# SCH_USB-Hub-with-audio-card_2025-04-20.net
KiCad netlist of a schematic drawn in EasyEDA
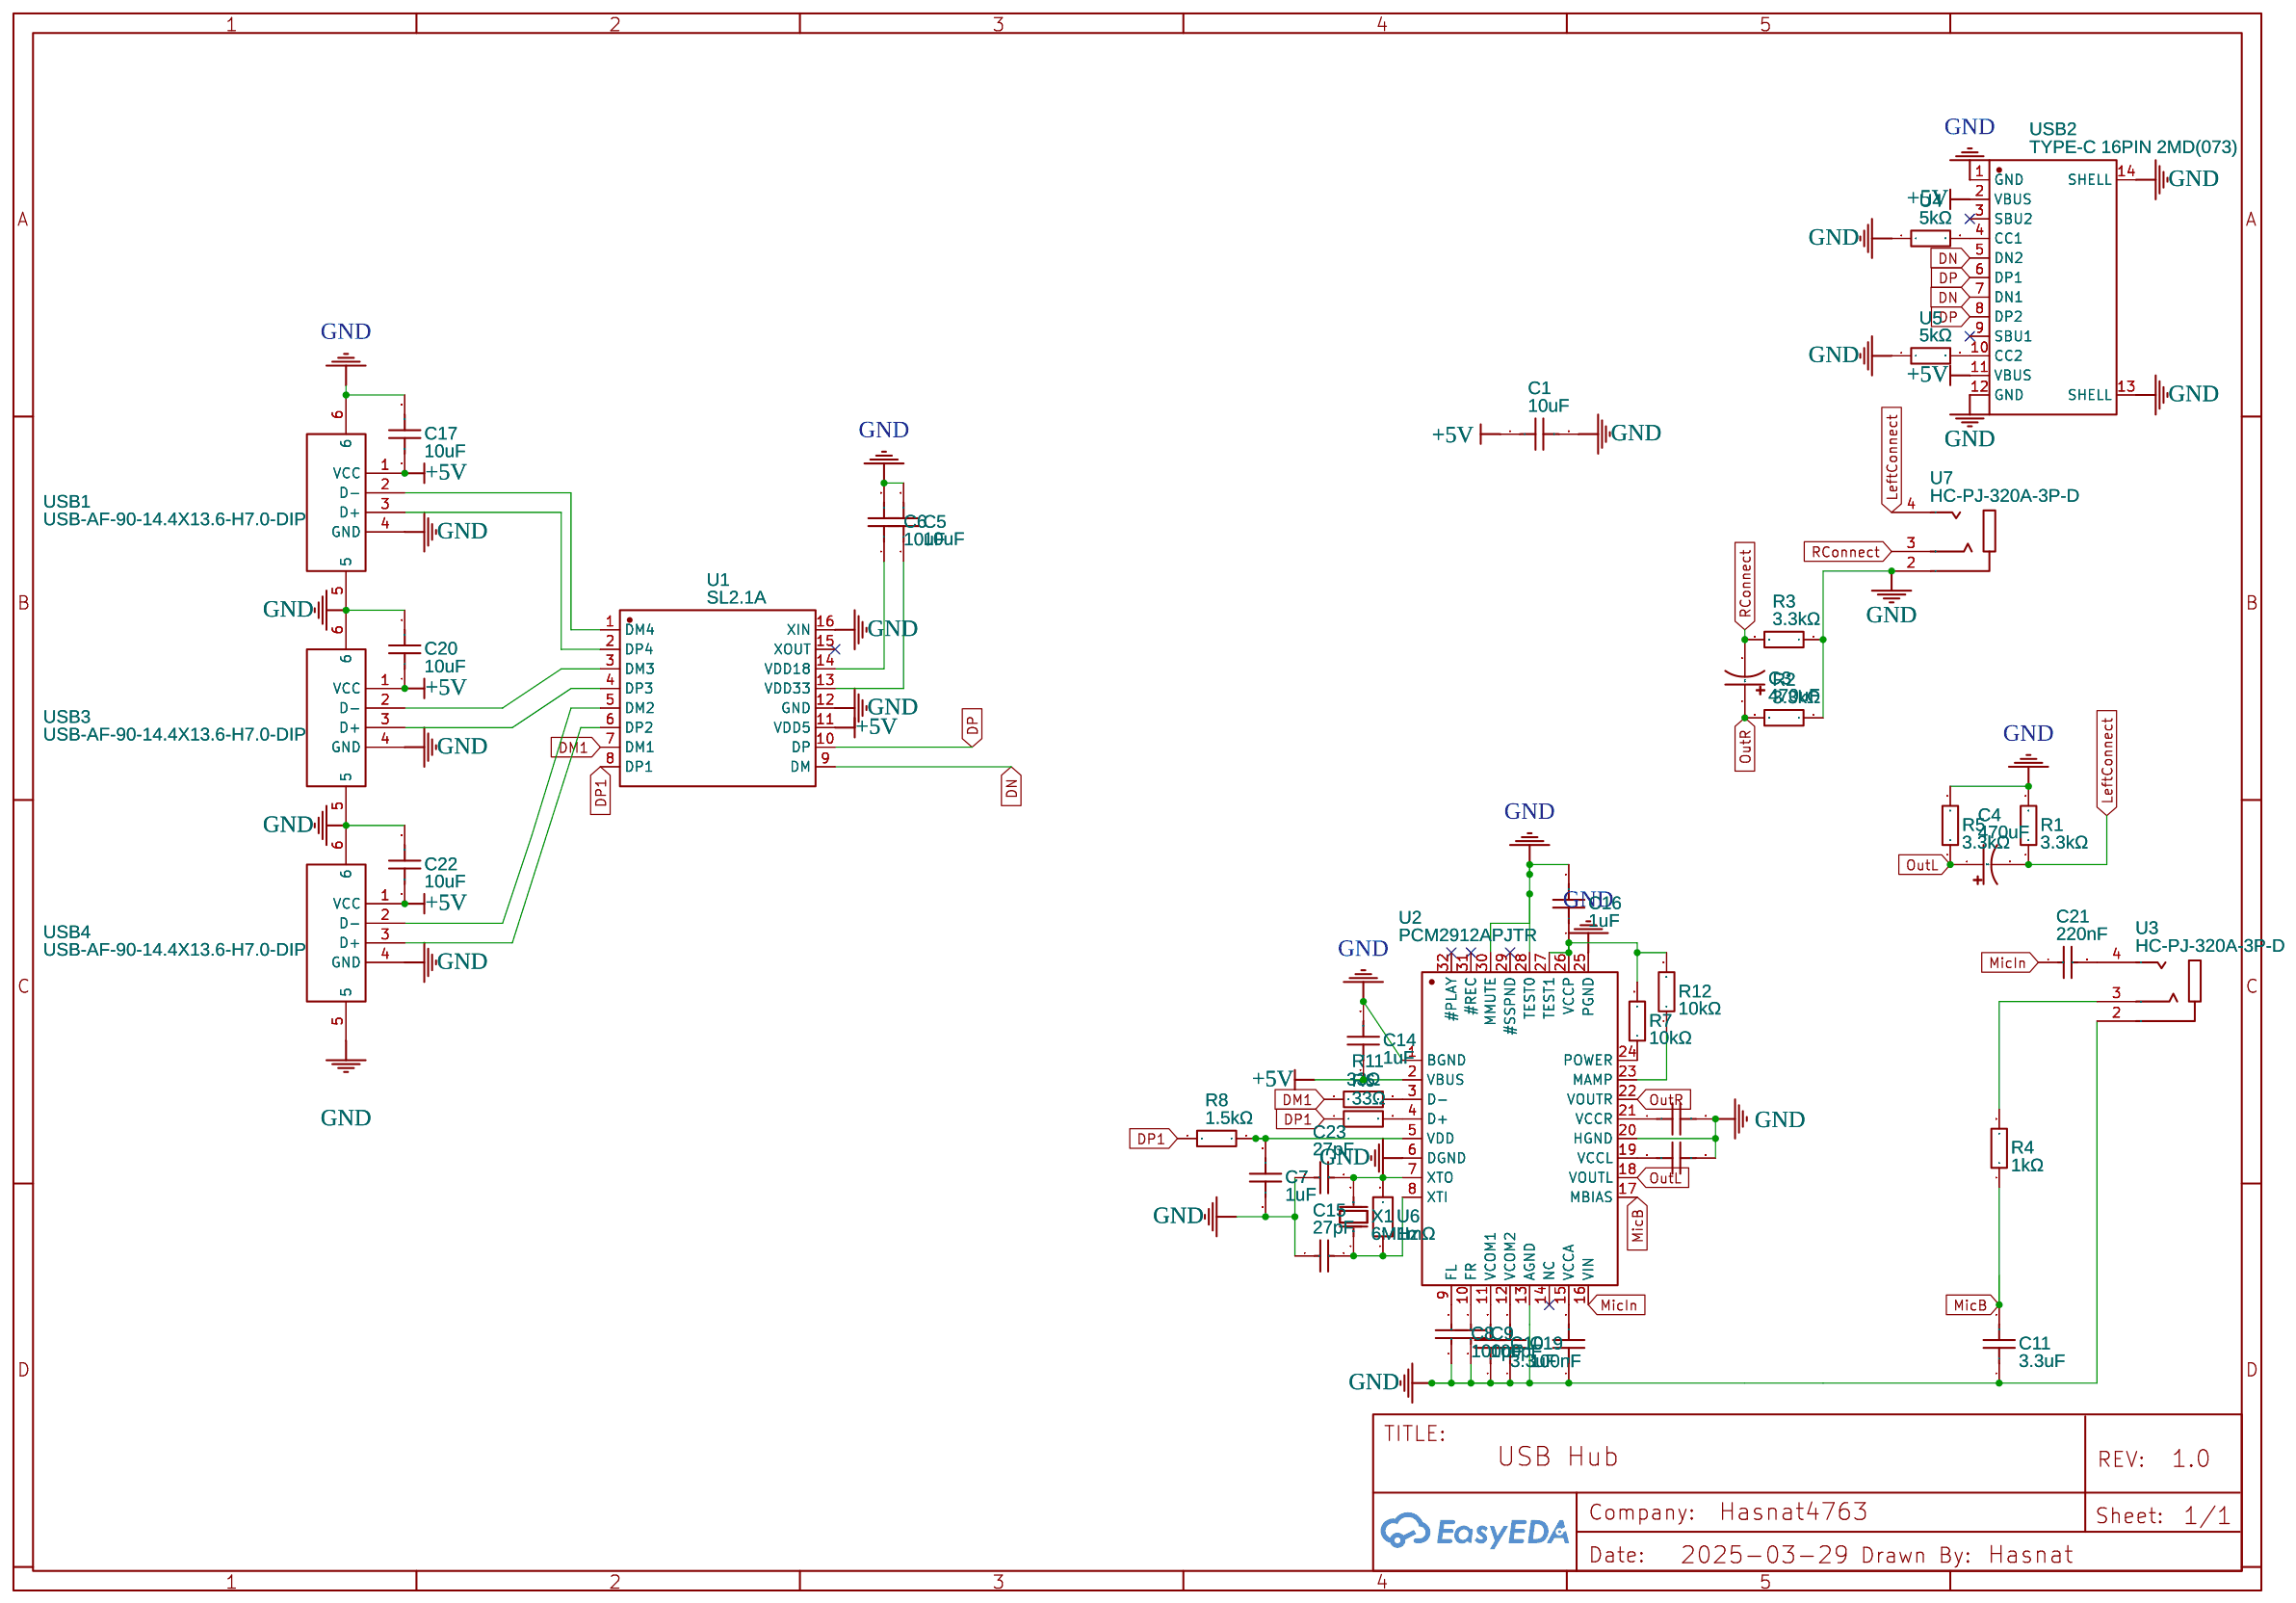
[diagram p0: schematic sheet]

(export (version "E")
  (design (tool "Eeschema 10.0.6"))
  (components
    (comp (ref "C1")
      (value "10uF")
      (fields
        (field (name "Manufacturer Part") "CL10A106KP8NNNC")
        (field (name "Manufacturer") "SAMSUNG(三星)")
      )
      (libsource (lib "") (part "CL10A106KP8NNNC"))
    )
    (comp (ref "C2")
      (value "1uF")
      (fields
        (field (name "Manufacturer Part") "CL31B105KBHNNNE")
        (field (name "Manufacturer") "SAMSUNG(三星)")
      )
      (libsource (lib "") (part "CL31B105KBHNNNE_1"))
    )
    (comp (ref "C3")
      (value "470uF")
      (fields (field (name "Manufacturer Part") "UKW1C471MPD") (field (name "Manufacturer") "Nichicon(尼吉康)"))
      (libsource (lib "") (part "UKW1C471MPD"))
    )
    (comp (ref "C4")
      (value "470uF")
      (fields (field (name "Manufacturer Part") "UKW1C471MPD") (field (name "Manufacturer") "Nichicon(尼吉康)"))
      (libsource (lib "") (part "UKW1C471MPD_1"))
    )
    (comp (ref "C5")
      (value "10uF")
      (fields
        (field (name "Manufacturer Part") "CL10A106KP8NNNC")
        (field (name "Manufacturer") "SAMSUNG(三星)")
      )
      (libsource (lib "") (part "CL10A106KP8NNNC_1"))
    )
    (comp (ref "C6")
      (value "10uF")
      (fields
        (field (name "Manufacturer Part") "CL10A106KP8NNNC")
        (field (name "Manufacturer") "SAMSUNG(三星)")
      )
      (libsource (lib "") (part "CL10A106KP8NNNC_1"))
    )
    (comp (ref "C7")
      (value "1uF")
      (fields
        (field (name "Manufacturer Part") "CL31B105KBHNNNE")
        (field (name "Manufacturer") "SAMSUNG(三星)")
      )
      (libsource (lib "") (part "CL31B105KBHNNNE_1"))
    )
    (comp (ref "C8")
      (value "100pF")
      (fields (field (name "Manufacturer Part") "0402CG101J500NT") (field (name "Manufacturer") "FH(风华)"))
      (libsource (lib "") (part "0402CG101J500NT"))
    )
    (comp (ref "C9")
      (value "100pF")
      (fields (field (name "Manufacturer Part") "0402CG101J500NT") (field (name "Manufacturer") "FH(风华)"))
      (libsource (lib "") (part "0402CG101J500NT"))
    )
    (comp (ref "C10")
      (value "3.3uF")
      (fields
        (field (name "Manufacturer Part") "GRM21BR71C335KA73L")
        (field (name "Manufacturer") "muRata(村田)")
      )
      (libsource (lib "") (part "GRM21BR71C335KA73L"))
    )
    (comp (ref "C11")
      (value "3.3uF")
      (fields
        (field (name "Manufacturer Part") "GRM21BR71C335KA73L")
        (field (name "Manufacturer") "muRata(村田)")
      )
      (libsource (lib "") (part "GRM21BR71C335KA73L"))
    )
    (comp (ref "C12")
      (value "1uF")
      (fields
        (field (name "Manufacturer Part") "CL31B105KBHNNNE")
        (field (name "Manufacturer") "SAMSUNG(三星)")
      )
      (libsource (lib "") (part "CL31B105KBHNNNE"))
    )
    (comp (ref "C13")
      (value "1uF")
      (fields
        (field (name "Manufacturer Part") "CL31B105KBHNNNE")
        (field (name "Manufacturer") "SAMSUNG(三星)")
      )
      (libsource (lib "") (part "CL31B105KBHNNNE"))
    )
    (comp (ref "C14")
      (value "1uF")
      (fields
        (field (name "Manufacturer Part") "CL31B105KBHNNNE")
        (field (name "Manufacturer") "SAMSUNG(三星)")
      )
      (libsource (lib "") (part "CL31B105KBHNNNE_1"))
    )
    (comp (ref "C15")
      (value "27pF")
      (fields (field (name "Manufacturer Part") "0402CG270J500NT") (field (name "Manufacturer") "FH(风华)"))
      (libsource (lib "") (part "0402CG270J500NTN"))
    )
    (comp (ref "C16")
      (value "1uF")
      (fields
        (field (name "Manufacturer Part") "CL31B105KBHNNNE")
        (field (name "Manufacturer") "SAMSUNG(三星)")
      )
      (libsource (lib "") (part "CL31B105KBHNNNE_1"))
    )
    (comp (ref "C17")
      (value "10uF")
      (fields
        (field (name "Manufacturer Part") "CL10A106KP8NNNC")
        (field (name "Manufacturer") "SAMSUNG(三星)")
      )
      (libsource (lib "") (part "CL10A106KP8NNNC_1"))
    )
    (comp (ref "C19")
      (value "100nF")
      (fields
        (field (name "Manufacturer Part") "CC0603KRX7R9BB104")
        (field (name "Manufacturer") "YAGEO(国巨)")
      )
      (libsource (lib "") (part "CC0603KRX7R9BB104"))
    )
    (comp (ref "C20")
      (value "10uF")
      (fields
        (field (name "Manufacturer Part") "CL10A106KP8NNNC")
        (field (name "Manufacturer") "SAMSUNG(三星)")
      )
      (libsource (lib "") (part "CL10A106KP8NNNC_1"))
    )
    (comp (ref "C21")
      (value "220nF")
      (fields
        (field (name "Manufacturer Part") "CL05B224KO5NNNC")
        (field (name "Manufacturer") "SAMSUNG(三星)")
      )
      (libsource (lib "") (part "CL05B224KO5NNNC"))
    )
    (comp (ref "C22")
      (value "10uF")
      (fields
        (field (name "Manufacturer Part") "CL10A106KP8NNNC")
        (field (name "Manufacturer") "SAMSUNG(三星)")
      )
      (libsource (lib "") (part "CL10A106KP8NNNC_1"))
    )
    (comp (ref "C23")
      (value "27pF")
      (fields (field (name "Manufacturer Part") "0402CG270J500NT") (field (name "Manufacturer") "FH(风华)"))
      (libsource (lib "") (part "0402CG270J500NTN"))
    )
    (comp (ref "R1")
      (value "3.3kΩ")
      (fields
        (field (name "Manufacturer Part") "0805W8F3301T5E")
        (field (name "Manufacturer") "UNI-ROYAL(厚声)")
      )
      (libsource (lib "") (part "0805W8F3301T5E_1"))
    )
    (comp (ref "R2")
      (value "3.3kΩ")
      (fields
        (field (name "Manufacturer Part") "0805W8F3301T5E")
        (field (name "Manufacturer") "UNI-ROYAL(厚声)")
      )
      (libsource (lib "") (part "0805W8F3301T5E"))
    )
    (comp (ref "R3")
      (value "3.3kΩ")
      (fields
        (field (name "Manufacturer Part") "0805W8F3301T5E")
        (field (name "Manufacturer") "UNI-ROYAL(厚声)")
      )
      (libsource (lib "") (part "0805W8F3301T5E"))
    )
    (comp (ref "R4")
      (value "1kΩ")
      (fields
        (field (name "Manufacturer Part") "0603WAF1001T5E")
        (field (name "Manufacturer") "UNI-ROYAL(厚声)")
      )
      (libsource (lib "") (part "0603WAF1001T5E"))
    )
    (comp (ref "R5")
      (value "3.3kΩ")
      (fields
        (field (name "Manufacturer Part") "0805W8F3301T5E")
        (field (name "Manufacturer") "UNI-ROYAL(厚声)")
      )
      (libsource (lib "") (part "0805W8F3301T5E_1"))
    )
    (comp (ref "R6")
      (value "33Ω")
      (fields
        (field (name "Manufacturer Part") "0603WAF330JT5E")
        (field (name "Manufacturer") "UNI-ROYAL(厚声)")
      )
      (libsource (lib "") (part "0603WAF330JT5E"))
    )
    (comp (ref "R7")
      (value "10kΩ")
      (fields
        (field (name "Manufacturer Part") "0603WAF1002T5E")
        (field (name "Manufacturer") "UNI-ROYAL(厚声)")
      )
      (libsource (lib "") (part "0603WAF1002T5E"))
    )
    (comp (ref "R8")
      (value "1.5kΩ")
      (fields
        (field (name "Manufacturer Part") "0603WAF1501T5E")
        (field (name "Manufacturer") "UNI-ROYAL(厚声)")
      )
      (libsource (lib "") (part "0603WAF1501T5E"))
    )
    (comp (ref "R11")
      (value "33Ω")
      (fields
        (field (name "Manufacturer Part") "0603WAF330JT5E")
        (field (name "Manufacturer") "UNI-ROYAL(厚声)")
      )
      (libsource (lib "") (part "0603WAF330JT5E"))
    )
    (comp (ref "R12")
      (value "10kΩ")
      (fields
        (field (name "Manufacturer Part") "0603WAF1002T5E")
        (field (name "Manufacturer") "UNI-ROYAL(厚声)")
      )
      (libsource (lib "") (part "0603WAF1002T5E"))
    )
    (comp (ref "U1")
      (value "SL2.1A")
      (fields (field (name "Manufacturer") "CoreChips(和芯润德)"))
      (libsource (lib "") (part "SL2.1A"))
    )
    (comp (ref "U2")
      (value "PCM2912APJTR")
      (fields (field (name "Manufacturer") "TI(德州仪器)"))
      (libsource (lib "") (part "PCM2912APJTR"))
    )
    (comp (ref "U3")
      (value "HC-PJ-320A-3P-D")
      (fields (field (name "Manufacturer") "HCTL(华灿天禄)"))
      (libsource (lib "") (part "HC-PJ-320A-3P-D"))
    )
    (comp (ref "U4")
      (value "5kΩ")
      (fields (field (name "Manufacturer Part") "MFP1WSBRD52-5K") (field (name "Manufacturer") "YAGEO(国巨)"))
      (libsource (lib "") (part "MFP1WSBRD52-5K"))
    )
    (comp (ref "U5")
      (value "5kΩ")
      (fields (field (name "Manufacturer Part") "MFP1WSBRD52-5K") (field (name "Manufacturer") "YAGEO(国巨)"))
      (libsource (lib "") (part "MFP1WSBRD52-5K"))
    )
    (comp (ref "U6")
      (value "1mΩ")
      (fields (field (name "Manufacturer Part") "MF0207FTE52-1M") (field (name "Manufacturer") "YAGEO(国巨)"))
      (libsource (lib "") (part "MF0207FTE52-1M"))
    )
    (comp (ref "U7")
      (value "HC-PJ-320A-3P-D")
      (fields (field (name "Manufacturer") "HCTL(华灿天禄)"))
      (libsource (lib "") (part "HC-PJ-320A-3P-D"))
    )
    (comp (ref "USB1")
      (value "USB-AF-90-14.4X13.6-H7.0-DIP")
      (fields (field (name "Manufacturer Part") "903-131A1011D10100") (field (name "Manufacturer") "精拓金"))
      (libsource (lib "") (part "USB-AF-90-14.4X13.6-H7.0-DIP"))
    )
    (comp (ref "USB2")
      (value "TYPE-C 16PIN 2MD(073)")
      (fields (field (name "Manufacturer") "SHOU HAN(首韩)"))
      (libsource (lib "") (part "TYPE-C 16PIN 2MD(073)"))
    )
    (comp (ref "USB3")
      (value "USB-AF-90-14.4X13.6-H7.0-DIP")
      (fields (field (name "Manufacturer Part") "903-131A1011D10100") (field (name "Manufacturer") "精拓金"))
      (libsource (lib "") (part "USB-AF-90-14.4X13.6-H7.0-DIP"))
    )
    (comp (ref "USB4")
      (value "USB-AF-90-14.4X13.6-H7.0-DIP")
      (fields (field (name "Manufacturer Part") "903-131A1011D10100") (field (name "Manufacturer") "精拓金"))
      (libsource (lib "") (part "USB-AF-90-14.4X13.6-H7.0-DIP"))
    )
    (comp (ref "X1")
      (value "6MHz")
      (fields (field (name "Manufacturer Part") "X49SM6MSD2SC") (field (name "Manufacturer") "YXC(扬兴晶振)"))
      (libsource (lib "") (part "X49SM6MSD2SC"))
    )
  )
  (nets
    (net (code "1") (name "+5V") (class "Default")
      (node (ref "C1") (pin "1") (pinfunction "1_1") (pintype "unspecified"))
      (node (ref "C14") (pin "1") (pinfunction "1_1") (pintype "unspecified"))
      (node (ref "C17") (pin "1") (pinfunction "1_1") (pintype "unspecified"))
      (node (ref "C20") (pin "1") (pinfunction "1_1") (pintype "unspecified"))
      (node (ref "C22") (pin "1") (pinfunction "1_1") (pintype "unspecified"))
      (node (ref "U1") (pin "11") (pinfunction "VDD5_11") (pintype "unspecified"))
      (node (ref "U2") (pin "2") (pinfunction "VBUS_2") (pintype "unspecified"))
      (node (ref "USB1") (pin "1") (pinfunction "VCC_1") (pintype "unspecified"))
      (node (ref "USB2") (pin "11") (pinfunction "VBUS_11") (pintype "unspecified"))
      (node (ref "USB2") (pin "2") (pinfunction "VBUS_2") (pintype "unspecified"))
      (node (ref "USB3") (pin "1") (pinfunction "VCC_1") (pintype "unspecified"))
      (node (ref "USB4") (pin "1") (pinfunction "VCC_1") (pintype "unspecified"))
    )
    (net (code "2") (name "DM1") (class "Default")
      (node (ref "R11") (pin "1") (pinfunction "1_1") (pintype "input"))
      (node (ref "U1") (pin "7") (pinfunction "DM1_7") (pintype "unspecified"))
    )
    (net (code "3") (name "DN") (class "Default")
      (node (ref "U1") (pin "9") (pinfunction "DM_9") (pintype "unspecified"))
      (node (ref "USB2") (pin "5") (pinfunction "DN2_5") (pintype "unspecified"))
      (node (ref "USB2") (pin "7") (pinfunction "DN1_7") (pintype "unspecified"))
    )
    (net (code "4") (name "DP") (class "Default")
      (node (ref "U1") (pin "10") (pinfunction "DP_10") (pintype "unspecified"))
      (node (ref "USB2") (pin "6") (pinfunction "DP1_6") (pintype "unspecified"))
      (node (ref "USB2") (pin "8") (pinfunction "DP2_8") (pintype "unspecified"))
    )
    (net (code "5") (name "DP1") (class "Default")
      (node (ref "R6") (pin "1") (pinfunction "1_1") (pintype "input"))
      (node (ref "R8") (pin "1") (pinfunction "1_1") (pintype "input"))
      (node (ref "U1") (pin "8") (pinfunction "DP1_8") (pintype "unspecified"))
    )
    (net (code "6") (name "GND") (class "Default")
      (node (ref "C1") (pin "2") (pinfunction "2_2") (pintype "unspecified"))
      (node (ref "C10") (pin "1") (pinfunction "1_1") (pintype "unspecified"))
      (node (ref "C11") (pin "1") (pinfunction "1_1") (pintype "unspecified"))
      (node (ref "C12") (pin "2") (pinfunction "2_2") (pintype "unspecified"))
      (node (ref "C13") (pin "2") (pinfunction "2_2") (pintype "unspecified"))
      (node (ref "C14") (pin "2") (pinfunction "2_2") (pintype "unspecified"))
      (node (ref "C15") (pin "1") (pinfunction "1_1") (pintype "input"))
      (node (ref "C16") (pin "2") (pinfunction "2_2") (pintype "unspecified"))
      (node (ref "C17") (pin "2") (pinfunction "2_2") (pintype "unspecified"))
      (node (ref "C19") (pin "1") (pinfunction "1_1") (pintype "unspecified"))
      (node (ref "C2") (pin "1") (pinfunction "1_1") (pintype "unspecified"))
      (node (ref "C20") (pin "2") (pinfunction "2_2") (pintype "unspecified"))
      (node (ref "C22") (pin "2") (pinfunction "2_2") (pintype "unspecified"))
      (node (ref "C23") (pin "1") (pinfunction "1_1") (pintype "input"))
      (node (ref "C5") (pin "2") (pinfunction "2_2") (pintype "unspecified"))
      (node (ref "C6") (pin "2") (pinfunction "2_2") (pintype "unspecified"))
      (node (ref "C7") (pin "1") (pinfunction "1_1") (pintype "unspecified"))
      (node (ref "C8") (pin "1") (pinfunction "1_1") (pintype "input"))
      (node (ref "C9") (pin "1") (pinfunction "1_1") (pintype "input"))
      (node (ref "R1") (pin "2") (pinfunction "2_2") (pintype "input"))
      (node (ref "R2") (pin "1") (pinfunction "1_1") (pintype "input"))
      (node (ref "R3") (pin "1") (pinfunction "1_1") (pintype "input"))
      (node (ref "R5") (pin "2") (pinfunction "2_2") (pintype "input"))
      (node (ref "U1") (pin "12") (pinfunction "GND_12") (pintype "unspecified"))
      (node (ref "U1") (pin "16") (pinfunction "XIN_16") (pintype "unspecified"))
      (node (ref "U2") (pin "1") (pinfunction "BGND_1") (pintype "unspecified"))
      (node (ref "U2") (pin "13") (pinfunction "AGND_13") (pintype "unspecified"))
      (node (ref "U2") (pin "20") (pinfunction "HGND_20") (pintype "unspecified"))
      (node (ref "U2") (pin "25") (pinfunction "PGND_25") (pintype "unspecified"))
      (node (ref "U2") (pin "28") (pinfunction "TEST0_28") (pintype "unspecified"))
      (node (ref "U2") (pin "30") (pinfunction "MMUTE_30") (pintype "unspecified"))
      (node (ref "U2") (pin "6") (pinfunction "DGND_6") (pintype "unspecified"))
      (node (ref "U3") (pin "2") (pinfunction "2_2") (pintype "unspecified"))
      (node (ref "U4") (pin "1") (pinfunction "1_1") (pintype "unspecified"))
      (node (ref "U5") (pin "1") (pinfunction "1_1") (pintype "unspecified"))
      (node (ref "U7") (pin "2") (pinfunction "2_2") (pintype "unspecified"))
      (node (ref "USB1") (pin "4") (pinfunction "GND_4") (pintype "unspecified"))
      (node (ref "USB1") (pin "5") (pinfunction "5_5") (pintype "unspecified"))
      (node (ref "USB1") (pin "6") (pinfunction "6_6") (pintype "unspecified"))
      (node (ref "USB2") (pin "1") (pinfunction "GND_1") (pintype "unspecified"))
      (node (ref "USB2") (pin "12") (pinfunction "GND_12") (pintype "unspecified"))
      (node (ref "USB2") (pin "13") (pinfunction "SHELL_13") (pintype "unspecified"))
      (node (ref "USB2") (pin "14") (pinfunction "SHELL_14") (pintype "unspecified"))
      (node (ref "USB3") (pin "4") (pinfunction "GND_4") (pintype "unspecified"))
      (node (ref "USB3") (pin "5") (pinfunction "5_5") (pintype "unspecified"))
      (node (ref "USB3") (pin "6") (pinfunction "6_6") (pintype "unspecified"))
      (node (ref "USB4") (pin "4") (pinfunction "GND_4") (pintype "unspecified"))
      (node (ref "USB4") (pin "5") (pinfunction "5_5") (pintype "unspecified"))
      (node (ref "USB4") (pin "6") (pinfunction "6_6") (pintype "unspecified"))
    )
    (net (code "7") (name "LeftConnect") (class "Default")
      (node (ref "C4") (pin "2") (pinfunction "2_2") (pintype "unspecified"))
      (node (ref "R1") (pin "1") (pinfunction "1_1") (pintype "input"))
      (node (ref "U7") (pin "4") (pinfunction "4_4") (pintype "unspecified"))
    )
    (net (code "8") (name "MicB") (class "Default")
      (node (ref "C11") (pin "2") (pinfunction "2_2") (pintype "unspecified"))
      (node (ref "R4") (pin "1") (pinfunction "1_1") (pintype "input"))
      (node (ref "U2") (pin "17") (pinfunction "MBIAS_17") (pintype "unspecified"))
    )
    (net (code "9") (name "MicIn") (class "Default")
      (node (ref "C21") (pin "1") (pinfunction "1_1") (pintype "input"))
      (node (ref "U2") (pin "16") (pinfunction "VIN_16") (pintype "unspecified"))
    )
    (net (code "10") (name "Net-(C21-Pad2)") (class "Default")
      (node (ref "C21") (pin "2") (pinfunction "2_2") (pintype "input"))
      (node (ref "U3") (pin "4") (pinfunction "4_4") (pintype "unspecified"))
    )
    (net (code "11") (name "Net-(R4-Pad2)") (class "Default")
      (node (ref "R4") (pin "2") (pinfunction "2_2") (pintype "input"))
      (node (ref "U3") (pin "3") (pinfunction "3_3") (pintype "unspecified"))
    )
    (net (code "12") (name "Net-(U1-DM2)") (class "Default")
      (node (ref "U1") (pin "5") (pinfunction "DM2_5") (pintype "unspecified"))
      (node (ref "USB4") (pin "2") (pinfunction "D-_2") (pintype "unspecified"))
    )
    (net (code "13") (name "Net-(U1-DM3)") (class "Default")
      (node (ref "U1") (pin "3") (pinfunction "DM3_3") (pintype "unspecified"))
      (node (ref "USB3") (pin "2") (pinfunction "D-_2") (pintype "unspecified"))
    )
    (net (code "14") (name "Net-(U1-DM4)") (class "Default")
      (node (ref "U1") (pin "1") (pinfunction "DM4_1") (pintype "unspecified"))
      (node (ref "USB1") (pin "2") (pinfunction "D-_2") (pintype "unspecified"))
    )
    (net (code "15") (name "Net-(U1-DP2)") (class "Default")
      (node (ref "U1") (pin "6") (pinfunction "DP2_6") (pintype "unspecified"))
      (node (ref "USB4") (pin "3") (pinfunction "D+_3") (pintype "unspecified"))
    )
    (net (code "16") (name "Net-(U1-DP3)") (class "Default")
      (node (ref "U1") (pin "4") (pinfunction "DP3_4") (pintype "unspecified"))
      (node (ref "USB3") (pin "3") (pinfunction "D+_3") (pintype "unspecified"))
    )
    (net (code "17") (name "Net-(U1-DP4)") (class "Default")
      (node (ref "U1") (pin "2") (pinfunction "DP4_2") (pintype "unspecified"))
      (node (ref "USB1") (pin "3") (pinfunction "D+_3") (pintype "unspecified"))
    )
    (net (code "18") (name "Net-(U1-VDD18)") (class "Default")
      (node (ref "C6") (pin "1") (pinfunction "1_1") (pintype "unspecified"))
      (node (ref "U1") (pin "14") (pinfunction "VDD18_14") (pintype "unspecified"))
    )
    (net (code "19") (name "Net-(U1-VDD33)") (class "Default")
      (node (ref "C5") (pin "1") (pinfunction "1_1") (pintype "unspecified"))
      (node (ref "U1") (pin "13") (pinfunction "VDD33_13") (pintype "unspecified"))
    )
    (net (code "20") (name "Net-(U2-D+)") (class "Default")
      (node (ref "R6") (pin "2") (pinfunction "2_2") (pintype "input"))
      (node (ref "U2") (pin "4") (pinfunction "D+_4") (pintype "unspecified"))
    )
    (net (code "21") (name "Net-(U2-D-)") (class "Default")
      (node (ref "R11") (pin "2") (pinfunction "2_2") (pintype "input"))
      (node (ref "U2") (pin "3") (pinfunction "D-_3") (pintype "unspecified"))
    )
    (net (code "22") (name "Net-(U2-FL)") (class "Default")
      (node (ref "C8") (pin "2") (pinfunction "2_2") (pintype "input"))
      (node (ref "U2") (pin "9") (pinfunction "FL_9") (pintype "unspecified"))
    )
    (net (code "23") (name "Net-(U2-FR)") (class "Default")
      (node (ref "C9") (pin "2") (pinfunction "2_2") (pintype "input"))
      (node (ref "U2") (pin "10") (pinfunction "FR_10") (pintype "unspecified"))
    )
    (net (code "24") (name "Net-(U2-MAMP)") (class "Default")
      (node (ref "R12") (pin "1") (pinfunction "1_1") (pintype "input"))
      (node (ref "U2") (pin "23") (pinfunction "MAMP_23") (pintype "unspecified"))
    )
    (net (code "25") (name "Net-(U2-POWER)") (class "Default")
      (node (ref "R7") (pin "1") (pinfunction "1_1") (pintype "input"))
      (node (ref "U2") (pin "24") (pinfunction "POWER_24") (pintype "unspecified"))
    )
    (net (code "26") (name "Net-(U2-TEST1)") (class "Default")
      (node (ref "C16") (pin "1") (pinfunction "1_1") (pintype "unspecified"))
      (node (ref "R12") (pin "2") (pinfunction "2_2") (pintype "input"))
      (node (ref "R7") (pin "2") (pinfunction "2_2") (pintype "input"))
      (node (ref "U2") (pin "26") (pinfunction "VCCP_26") (pintype "unspecified"))
      (node (ref "U2") (pin "27") (pinfunction "TEST1_27") (pintype "unspecified"))
    )
    (net (code "27") (name "Net-(U2-VCCA)") (class "Default")
      (node (ref "C2") (pin "2") (pinfunction "2_2") (pintype "unspecified"))
      (node (ref "U2") (pin "15") (pinfunction "VCCA_15") (pintype "unspecified"))
    )
    (net (code "28") (name "Net-(U2-VCCL)") (class "Default")
      (node (ref "C13") (pin "1") (pinfunction "1_1") (pintype "unspecified"))
      (node (ref "U2") (pin "19") (pinfunction "VCCL_19") (pintype "unspecified"))
    )
    (net (code "29") (name "Net-(U2-VCCR)") (class "Default")
      (node (ref "C12") (pin "1") (pinfunction "1_1") (pintype "unspecified"))
      (node (ref "U2") (pin "21") (pinfunction "VCCR_21") (pintype "unspecified"))
    )
    (net (code "30") (name "Net-(U2-VCOM1)") (class "Default")
      (node (ref "C10") (pin "2") (pinfunction "2_2") (pintype "unspecified"))
      (node (ref "U2") (pin "11") (pinfunction "VCOM1_11") (pintype "unspecified"))
    )
    (net (code "31") (name "Net-(U2-VCOM2)") (class "Default")
      (node (ref "C19") (pin "2") (pinfunction "2_2") (pintype "unspecified"))
      (node (ref "U2") (pin "12") (pinfunction "VCOM2_12") (pintype "unspecified"))
    )
    (net (code "32") (name "Net-(U2-VDD)") (class "Default")
      (node (ref "C7") (pin "2") (pinfunction "2_2") (pintype "unspecified"))
      (node (ref "R8") (pin "2") (pinfunction "2_2") (pintype "input"))
      (node (ref "U2") (pin "5") (pinfunction "VDD_5") (pintype "unspecified"))
    )
    (net (code "33") (name "Net-(U2-XTI)") (class "Default")
      (node (ref "C15") (pin "2") (pinfunction "2_2") (pintype "input"))
      (node (ref "U2") (pin "8") (pinfunction "XTI_8") (pintype "unspecified"))
      (node (ref "U6") (pin "1") (pinfunction "1_1") (pintype "unspecified"))
      (node (ref "X1") (pin "1") (pinfunction "OSC1_1") (pintype "input"))
    )
    (net (code "34") (name "Net-(U2-XTO)") (class "Default")
      (node (ref "C23") (pin "2") (pinfunction "2_2") (pintype "input"))
      (node (ref "U2") (pin "7") (pinfunction "XTO_7") (pintype "unspecified"))
      (node (ref "U6") (pin "2") (pinfunction "2_2") (pintype "unspecified"))
      (node (ref "X1") (pin "2") (pinfunction "OSC2_2") (pintype "input"))
    )
    (net (code "35") (name "Net-(USB2-CC1)") (class "Default")
      (node (ref "U4") (pin "2") (pinfunction "2_2") (pintype "unspecified"))
      (node (ref "USB2") (pin "4") (pinfunction "CC1_4") (pintype "unspecified"))
    )
    (net (code "36") (name "Net-(USB2-CC2)") (class "Default")
      (node (ref "U5") (pin "2") (pinfunction "2_2") (pintype "unspecified"))
      (node (ref "USB2") (pin "10") (pinfunction "CC2_10") (pintype "unspecified"))
    )
    (net (code "37") (name "OutL") (class "Default")
      (node (ref "C4") (pin "1") (pinfunction "1_1") (pintype "unspecified"))
      (node (ref "R5") (pin "1") (pinfunction "1_1") (pintype "input"))
      (node (ref "U2") (pin "18") (pinfunction "VOUTL_18") (pintype "unspecified"))
    )
    (net (code "38") (name "OutR") (class "Default")
      (node (ref "C3") (pin "1") (pinfunction "1_1") (pintype "unspecified"))
      (node (ref "R2") (pin "2") (pinfunction "2_2") (pintype "input"))
      (node (ref "U2") (pin "22") (pinfunction "VOUTR_22") (pintype "unspecified"))
    )
    (net (code "39") (name "RConnect") (class "Default")
      (node (ref "C3") (pin "2") (pinfunction "2_2") (pintype "unspecified"))
      (node (ref "R3") (pin "2") (pinfunction "2_2") (pintype "input"))
      (node (ref "U7") (pin "3") (pinfunction "3_3") (pintype "unspecified"))
    )
    (net (code "40") (name "unconnected-(U1-XOUT-Pad15)") (class "Default")
      (node (ref "U1") (pin "15") (pinfunction "XOUT_15") (pintype "unspecified+no_connect"))
    )
    (net (code "41") (name "unconnected-(U2-#PLAY-Pad32)") (class "Default")
      (node (ref "U2") (pin "32") (pinfunction "#PLAY_32") (pintype "unspecified+no_connect"))
    )
    (net (code "42") (name "unconnected-(U2-#REC-Pad31)") (class "Default")
      (node (ref "U2") (pin "31") (pinfunction "#REC_31") (pintype "unspecified+no_connect"))
    )
    (net (code "43") (name "unconnected-(U2-#SSPND-Pad29)") (class "Default")
      (node (ref "U2") (pin "29") (pinfunction "#SSPND_29") (pintype "unspecified+no_connect"))
    )
    (net (code "44") (name "unconnected-(U2-NC-Pad14)") (class "Default")
      (node (ref "U2") (pin "14") (pinfunction "NC_14") (pintype "unspecified+no_connect"))
    )
    (net (code "45") (name "unconnected-(USB2-SBU1-Pad9)") (class "Default")
      (node (ref "USB2") (pin "9") (pinfunction "SBU1_9") (pintype "unspecified+no_connect"))
    )
    (net (code "46") (name "unconnected-(USB2-SBU2-Pad3)") (class "Default")
      (node (ref "USB2") (pin "3") (pinfunction "SBU2_3") (pintype "unspecified+no_connect"))
    )
  )
)
